# SSB_Transceiver_TXPWR-Switch.net
KiCad netlist of a schematic drawn in EAGLE
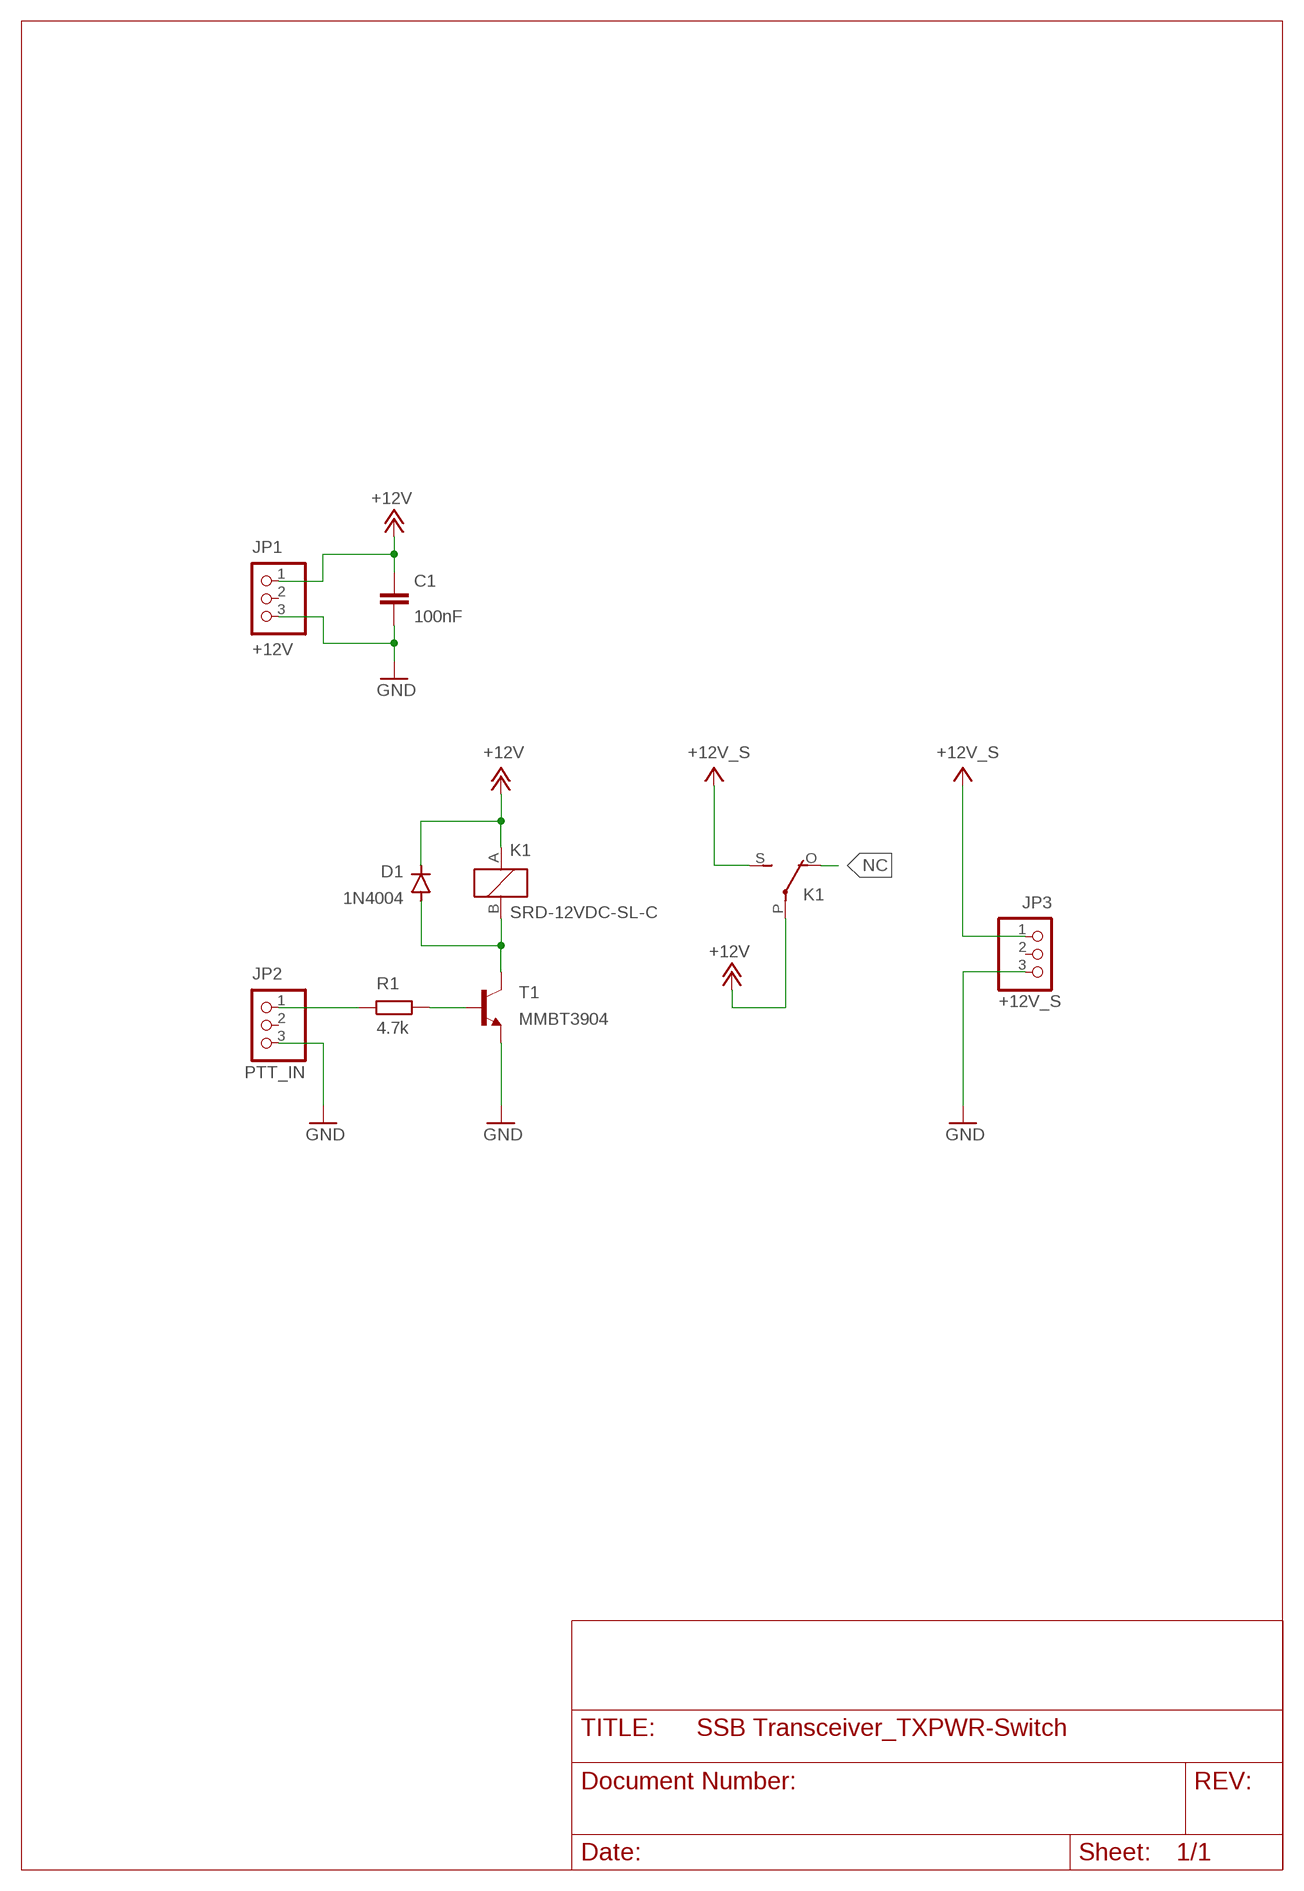
[diagram p0: schematic, sheet 1]

(export (version "E")
  (design (tool "Eeschema 10.0.6"))
  (components
    (comp (ref "C1")
      (value "100nF")
      (footprint "eagle-import:C0805K")
      (libsource (lib "eagle-import") (part "C-EUC0805K"))
    )
    (comp (ref "D1")
      (value "1N4004")
      (footprint "eagle-import:DO41-10")
      (libsource (lib "eagle-import") (part "1N4004"))
    )
    (comp (ref "JP1")
      (value "+12V")
      (footprint "eagle-import:1X03")
      (libsource (lib "eagle-import") (part "PINHD-1X3"))
    )
    (comp (ref "JP2")
      (value "PTT_IN")
      (footprint "eagle-import:1X03")
      (libsource (lib "eagle-import") (part "PINHD-1X3"))
    )
    (comp (ref "JP3")
      (value "+12V_S")
      (footprint "eagle-import:1X03")
      (libsource (lib "eagle-import") (part "PINHD-1X3"))
    )
    (comp (ref "K1")
      (value "SRD-12VDC-SL-C")
      (footprint "eagle-import:SRD-12VDC-SL-C")
      (libsource (lib "eagle-import") (part "SRD-12VDC-SL-C"))
    )
    (comp (ref "R1")
      (value "4.7k")
      (footprint "eagle-import:R0805")
      (libsource (lib "eagle-import") (part "R-EU_R0805"))
    )
    (comp (ref "T1")
      (value "MMBT3904")
      (footprint "eagle-import:SOT23-BEC")
      (libsource (lib "eagle-import") (part "-NPN-SOT23-BECMMBT3904LT1"))
    )
  )
  (nets
    (net (code "1") (name "+12V") (class "Default")
      (node (ref "C1") (pin "1") (pinfunction "1_1") (pintype "passive"))
      (node (ref "D1") (pin "C") (pinfunction "C_C") (pintype "passive"))
      (node (ref "JP1") (pin "1") (pinfunction "1_1") (pintype "passive"))
      (node (ref "K1") (pin "A") (pinfunction "A_A") (pintype "passive"))
      (node (ref "K1") (pin "P") (pinfunction "P_P") (pintype "passive"))
    )
    (net (code "2") (name "+12V_S") (class "Default")
      (node (ref "JP3") (pin "1") (pinfunction "1_1") (pintype "passive"))
      (node (ref "K1") (pin "S") (pinfunction "S_S") (pintype "passive"))
    )
    (net (code "3") (name "GND") (class "Default")
      (node (ref "C1") (pin "2") (pinfunction "2_2") (pintype "passive"))
      (node (ref "JP1") (pin "3") (pinfunction "3_3") (pintype "passive"))
      (node (ref "JP2") (pin "3") (pinfunction "3_3") (pintype "passive"))
      (node (ref "JP3") (pin "3") (pinfunction "3_3") (pintype "passive"))
      (node (ref "T1") (pin "E") (pinfunction "E_E") (pintype "passive"))
    )
    (net (code "4") (name "NC") (class "Default")
      (node (ref "K1") (pin "O") (pinfunction "O_O") (pintype "passive"))
    )
    (net (code "5") (name "Net-(D1-PadA)") (class "Default")
      (node (ref "D1") (pin "A") (pinfunction "A_A") (pintype "passive"))
      (node (ref "K1") (pin "B") (pinfunction "B_B") (pintype "passive"))
      (node (ref "T1") (pin "C") (pinfunction "C_C") (pintype "passive"))
    )
    (net (code "6") (name "Net-(JP2-Pad1)") (class "Default")
      (node (ref "JP2") (pin "1") (pinfunction "1_1") (pintype "passive"))
      (node (ref "R1") (pin "1") (pinfunction "1_1") (pintype "passive"))
    )
    (net (code "7") (name "Net-(R1-Pad2)") (class "Default")
      (node (ref "R1") (pin "2") (pinfunction "2_2") (pintype "passive"))
      (node (ref "T1") (pin "B") (pinfunction "B_B") (pintype "passive"))
    )
    (net (code "8") (name "unconnected-(JP1-Pad2)") (class "Default")
      (node (ref "JP1") (pin "2") (pinfunction "2_2") (pintype "passive"))
    )
    (net (code "9") (name "unconnected-(JP2-Pad2)") (class "Default")
      (node (ref "JP2") (pin "2") (pinfunction "2_2") (pintype "passive"))
    )
    (net (code "10") (name "unconnected-(JP3-Pad2)") (class "Default")
      (node (ref "JP3") (pin "2") (pinfunction "2_2") (pintype "passive"))
    )
  )
)
